# v1_0.net
KiCad netlist of a schematic drawn in Altium Designer
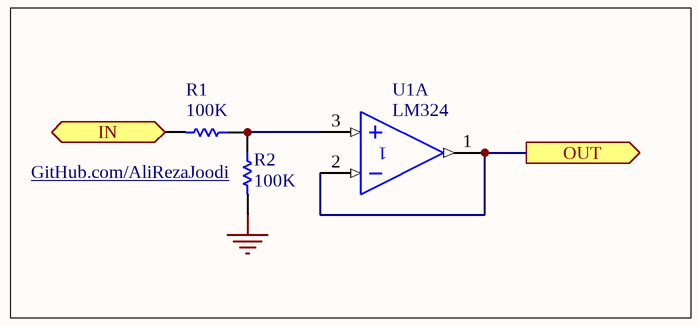
[diagram p0: v1.0.SchDoc]

(export (version "E")
  (design (tool "Eeschema 10.0.6"))
  (components
    (comp (ref "R1")
      (value "100K")
      (footprint "AXIAL-0.4")
      (description "Resistor")
      (fields (field (name "PUBLISHER") "Altium Limited"))
      (libsource (lib "Miscellaneous Devices") (part "Res1"))
    )
    (comp (ref "R2")
      (value "100K")
      (footprint "AXIAL-0.4")
      (description "Resistor")
      (fields (field (name "PUBLISHER") "Altium Limited"))
      (libsource (lib "Miscellaneous Devices") (part "Res1"))
    )
    (comp (ref "U1")
      (value "LM324")
      (footprint "646-06")
      (description "Quad Low-Power Operational Amplifier")
      (fields (field (name "PUBLISHER") "Altium Limited"))
      (libsource (lib "my Libraries") (part "LM324"))
    )
  )
  (nets
    (net (code "1") (name "/IN") (class "Default")
      (node (ref "R1") (pin "2") (pinfunction "2_2") (pintype "passive"))
    )
    (net (code "2") (name "/OUT") (class "Default")
      (node (ref "U1") (pin "1") (pinfunction "OUT_1") (pintype "output"))
      (node (ref "U1") (pin "2") (pinfunction "IN-_2") (pintype "input"))
    )
    (net (code "3") (name "GND") (class "Default")
      (node (ref "R2") (pin "2") (pinfunction "2_2") (pintype "passive"))
    )
    (net (code "4") (name "Net-(U1A-IN+)") (class "Default")
      (node (ref "R1") (pin "1") (pinfunction "1_1") (pintype "passive"))
      (node (ref "R2") (pin "1") (pinfunction "1_1") (pintype "passive"))
      (node (ref "U1") (pin "3") (pinfunction "IN+_3") (pintype "input"))
    )
  )
)
